# lab4.net
KiCad netlist of a schematic drawn in EAGLE
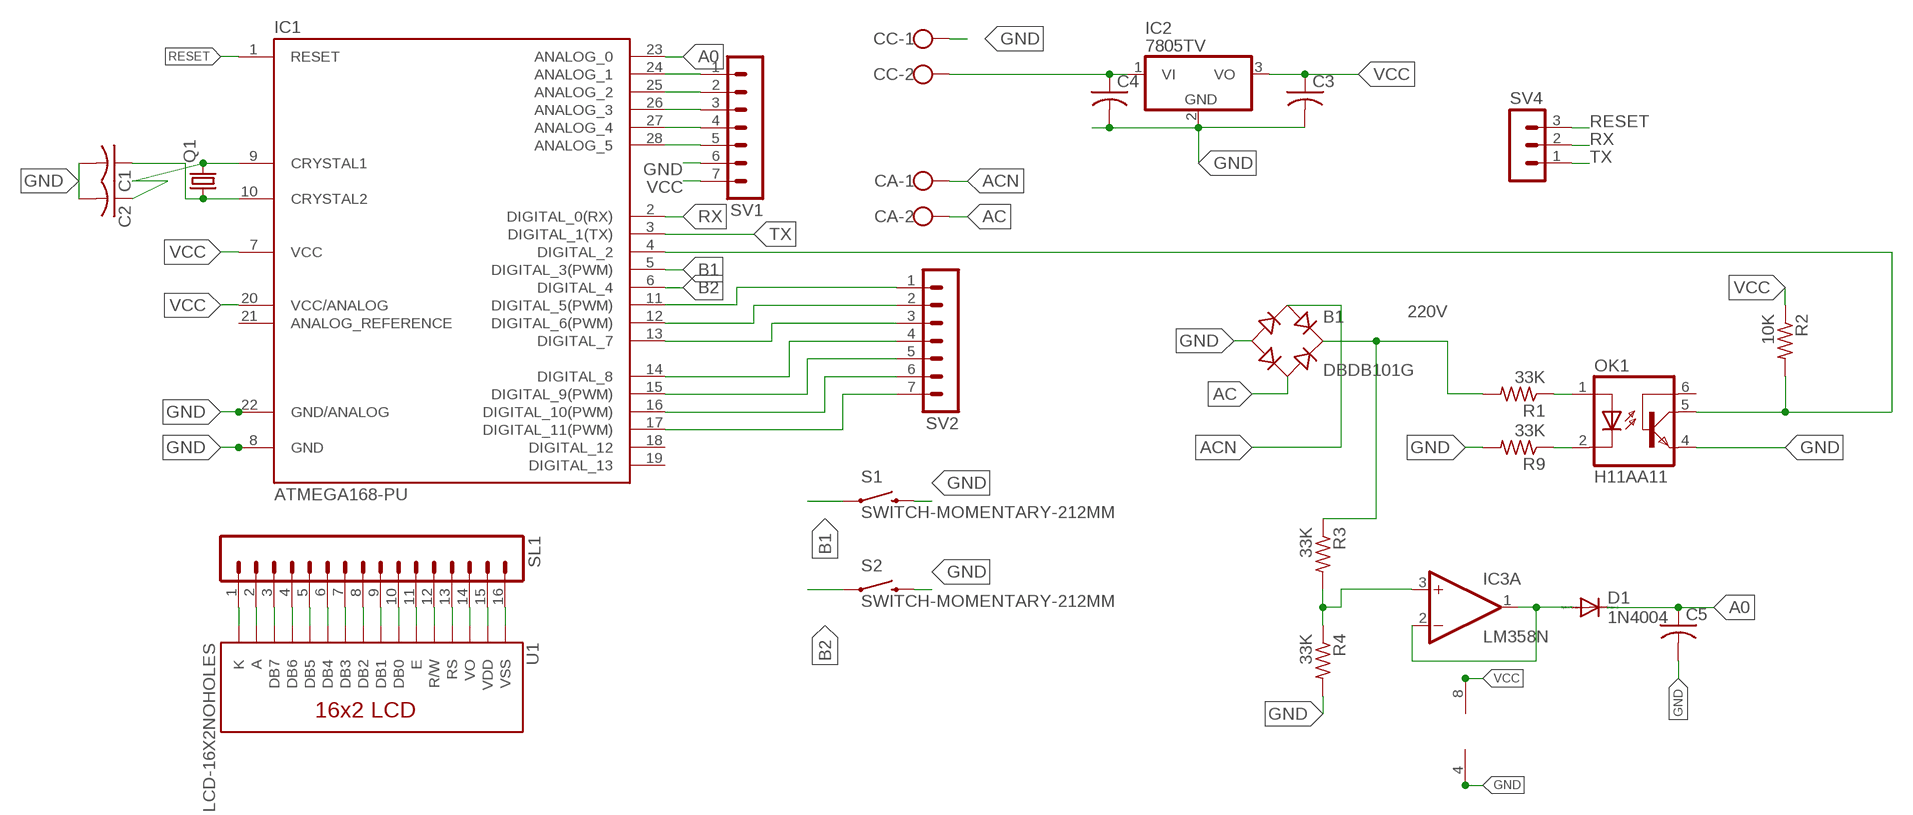
[diagram p0: schematic, sheet 1]

(export (version "E")
  (design (tool "Eeschema 10.0.6"))
  (components
    (comp (ref "B1")
      (value "DBDB101G")
      (footprint "eagle-import:DB")
      (libsource (lib "eagle-import") (part "DB?GDB101"))
    )
    (comp (ref "C1")
      (value "C-US025-025X050")
      (footprint "eagle-import:C025-025X050")
      (libsource (lib "eagle-import") (part "C-US025-025X050"))
    )
    (comp (ref "C2")
      (value "C-US025-025X050")
      (footprint "eagle-import:C025-025X050")
      (libsource (lib "eagle-import") (part "C-US025-025X050"))
    )
    (comp (ref "C3")
      (value "C-US075-032X103")
      (footprint "eagle-import:C075-032X103")
      (libsource (lib "eagle-import") (part "C-US075-032X103"))
    )
    (comp (ref "C4")
      (value "C-US050-025X075")
      (footprint "eagle-import:C050-025X075")
      (libsource (lib "eagle-import") (part "C-US050-025X075"))
    )
    (comp (ref "C5")
      (value "C-US050-075X075")
      (footprint "eagle-import:C050-075X075")
      (libsource (lib "eagle-import") (part "C-US050-075X075"))
    )
    (comp (ref "CA")
      (value "W237-102")
      (footprint "eagle-import:W237-102")
      (fields (field (name "MPN") "237-102"))
      (libsource (lib "eagle-import") (part "W237-102"))
    )
    (comp (ref "CC")
      (value "W237-102")
      (footprint "eagle-import:W237-102")
      (fields (field (name "MPN") "237-102"))
      (libsource (lib "eagle-import") (part "W237-102"))
    )
    (comp (ref "D1")
      (value "1N4004")
      (footprint "eagle-import:DO41-10")
      (libsource (lib "eagle-import") (part "1N4004"))
    )
    (comp (ref "IC1")
      (value "ATMEGA168-PU")
      (footprint "eagle-import:DIL28-3")
      (libsource (lib "eagle-import") (part "ATMEGA168-PU"))
    )
    (comp (ref "IC2")
      (value "7805TV")
      (footprint "eagle-import:TO220V")
      (libsource (lib "eagle-import") (part "78TV05"))
    )
    (comp (ref "IC3")
      (value "LM358N")
      (footprint "eagle-import:DIL08")
      (libsource (lib "eagle-import") (part "LM358N"))
    )
    (comp (ref "OK1")
      (value "H11AA11")
      (footprint "eagle-import:DIL06")
      (fields (field (name "MPN") "H11A1-M"))
      (libsource (lib "eagle-import") (part "H11AA11"))
    )
    (comp (ref "Q1")
      (value "CRYSTALHC18U-V")
      (footprint "eagle-import:HC18U-V")
      (libsource (lib "eagle-import") (part "CRYSTALHC18U-V"))
    )
    (comp (ref "R1")
      (value "33K")
      (footprint "eagle-import:0207_7")
      (libsource (lib "eagle-import") (part "R-US_0207/7"))
    )
    (comp (ref "R2")
      (value "10K")
      (footprint "eagle-import:0309_12")
      (libsource (lib "eagle-import") (part "R-US_0309/12"))
    )
    (comp (ref "R3")
      (value "33K")
      (footprint "eagle-import:0207_7")
      (libsource (lib "eagle-import") (part "R-US_0207/7"))
    )
    (comp (ref "R4")
      (value "33K")
      (footprint "eagle-import:0207_7")
      (libsource (lib "eagle-import") (part "R-US_0207/7"))
    )
    (comp (ref "R9")
      (value "33K")
      (footprint "eagle-import:0207_7")
      (libsource (lib "eagle-import") (part "R-US_0207/7"))
    )
    (comp (ref "S1")
      (value "SWITCH-MOMENTARY-212MM")
      (footprint "eagle-import:TACTILE-PTH-12MM")
      (libsource (lib "eagle-import") (part "SWITCH-MOMENTARY-212MM"))
    )
    (comp (ref "S2")
      (value "SWITCH-MOMENTARY-212MM")
      (footprint "eagle-import:TACTILE-PTH-12MM")
      (libsource (lib "eagle-import") (part "SWITCH-MOMENTARY-212MM"))
    )
    (comp (ref "SL1")
      (value "MA16")
      (footprint "eagle-import:16PA")
      (libsource (lib "eagle-import") (part "MA16"))
    )
    (comp (ref "SV1")
      (value "MA07-1")
      (footprint "eagle-import:MA07-1")
      (libsource (lib "eagle-import") (part "MA07-1"))
    )
    (comp (ref "SV2")
      (value "MA07-1")
      (footprint "eagle-import:MA07-1")
      (libsource (lib "eagle-import") (part "MA07-1"))
    )
    (comp (ref "SV4")
      (value "MA03-1")
      (footprint "eagle-import:MA03-1")
      (libsource (lib "eagle-import") (part "MA03-1"))
    )
    (comp (ref "U1")
      (value "LCD-16X2NOHOLES")
      (footprint "eagle-import:LCD-16X2_NOHOLES")
      (libsource (lib "eagle-import") (part "LCD-16X2NOHOLES"))
    )
  )
  (nets
    (net (code "1") (name "/220V") (class "Default")
      (node (ref "B1") (pin "+") (pinfunction "+_+") (pintype "passive"))
      (node (ref "R1") (pin "2") (pinfunction "2_2") (pintype "passive"))
      (node (ref "R3") (pin "1") (pinfunction "1_1") (pintype "passive"))
    )
    (net (code "2") (name "A0") (class "Default")
      (node (ref "C5") (pin "1") (pinfunction "1_1") (pintype "passive"))
      (node (ref "D1") (pin "C") (pinfunction "C_C") (pintype "passive"))
      (node (ref "IC1") (pin "23") (pinfunction "ANALOG_0_23") (pintype "bidirectional"))
    )
    (net (code "3") (name "AC") (class "Default")
      (node (ref "B1") (pin "AC2") (pinfunction "AC2_AC2") (pintype "passive"))
      (node (ref "CA") (pin "2") (pinfunction "KL_2") (pintype "passive"))
    )
    (net (code "4") (name "ACN") (class "Default")
      (node (ref "B1") (pin "AC1") (pinfunction "AC1_AC1") (pintype "passive"))
      (node (ref "CA") (pin "1") (pinfunction "KL_1") (pintype "passive"))
    )
    (net (code "5") (name "B1") (class "Default")
      (node (ref "IC1") (pin "5") (pinfunction "DIGITAL_3(PWM)_5") (pintype "bidirectional"))
      (node (ref "S1") (pin "1") (pinfunction "1_1") (pintype "passive"))
    )
    (net (code "6") (name "B2") (class "Default")
      (node (ref "IC1") (pin "6") (pinfunction "DIGITAL_4_6") (pintype "bidirectional"))
      (node (ref "S2") (pin "1") (pinfunction "1_1") (pintype "passive"))
    )
    (net (code "7") (name "GND") (class "Default")
      (node (ref "B1") (pin "-") (pinfunction "-_-") (pintype "passive"))
      (node (ref "C1") (pin "2") (pinfunction "2_2") (pintype "passive"))
      (node (ref "C2") (pin "2") (pinfunction "2_2") (pintype "passive"))
      (node (ref "C3") (pin "2") (pinfunction "2_2") (pintype "passive"))
      (node (ref "C4") (pin "2") (pinfunction "2_2") (pintype "passive"))
      (node (ref "C5") (pin "2") (pinfunction "2_2") (pintype "passive"))
      (node (ref "CC") (pin "1") (pinfunction "KL_1") (pintype "passive"))
      (node (ref "IC1") (pin "22") (pinfunction "GND/ANALOG_22") (pintype "power_in"))
      (node (ref "IC1") (pin "8") (pinfunction "GND_8") (pintype "power_in"))
      (node (ref "IC2") (pin "2") (pinfunction "GND_2") (pintype "passive"))
      (node (ref "IC3") (pin "4") (pinfunction "V-_4") (pintype "power_in"))
      (node (ref "OK1") (pin "4") (pinfunction "EMI_4") (pintype "passive"))
      (node (ref "R4") (pin "2") (pinfunction "2_2") (pintype "passive"))
      (node (ref "R9") (pin "2") (pinfunction "2_2") (pintype "passive"))
      (node (ref "S1") (pin "3") (pinfunction "2_3") (pintype "passive"))
      (node (ref "S2") (pin "3") (pinfunction "2_3") (pintype "passive"))
      (node (ref "SV1") (pin "6") (pinfunction "6_6") (pintype "passive"))
    )
    (net (code "8") (name "Net-(CCB-KL)") (class "Default")
      (node (ref "C4") (pin "1") (pinfunction "1_1") (pintype "passive"))
      (node (ref "CC") (pin "2") (pinfunction "KL_2") (pintype "passive"))
      (node (ref "IC2") (pin "1") (pinfunction "VI_1") (pintype "input"))
    )
    (net (code "9") (name "Net-(IC1-ANALOG_1)") (class "Default")
      (node (ref "IC1") (pin "24") (pinfunction "ANALOG_1_24") (pintype "bidirectional"))
      (node (ref "SV1") (pin "1") (pinfunction "1_1") (pintype "passive"))
    )
    (net (code "10") (name "Net-(IC1-ANALOG_2)") (class "Default")
      (node (ref "IC1") (pin "25") (pinfunction "ANALOG_2_25") (pintype "bidirectional"))
      (node (ref "SV1") (pin "2") (pinfunction "2_2") (pintype "passive"))
    )
    (net (code "11") (name "Net-(IC1-ANALOG_3)") (class "Default")
      (node (ref "IC1") (pin "26") (pinfunction "ANALOG_3_26") (pintype "bidirectional"))
      (node (ref "SV1") (pin "3") (pinfunction "3_3") (pintype "passive"))
    )
    (net (code "12") (name "Net-(IC1-ANALOG_4)") (class "Default")
      (node (ref "IC1") (pin "27") (pinfunction "ANALOG_4_27") (pintype "bidirectional"))
      (node (ref "SV1") (pin "4") (pinfunction "4_4") (pintype "passive"))
    )
    (net (code "13") (name "Net-(IC1-ANALOG_5)") (class "Default")
      (node (ref "IC1") (pin "28") (pinfunction "ANALOG_5_28") (pintype "bidirectional"))
      (node (ref "SV1") (pin "5") (pinfunction "5_5") (pintype "passive"))
    )
    (net (code "14") (name "Net-(IC1-CRYSTAL1)") (class "Default")
      (node (ref "C2") (pin "1") (pinfunction "1_1") (pintype "passive"))
      (node (ref "IC1") (pin "9") (pinfunction "CRYSTAL1_9") (pintype "bidirectional"))
      (node (ref "Q1") (pin "2") (pinfunction "2_2") (pintype "passive"))
    )
    (net (code "15") (name "Net-(IC1-CRYSTAL2)") (class "Default")
      (node (ref "C1") (pin "1") (pinfunction "1_1") (pintype "passive"))
      (node (ref "IC1") (pin "10") (pinfunction "CRYSTAL2_10") (pintype "bidirectional"))
      (node (ref "Q1") (pin "1") (pinfunction "1_1") (pintype "passive"))
    )
    (net (code "16") (name "Net-(IC1-DIGITAL_2)") (class "Default")
      (node (ref "IC1") (pin "4") (pinfunction "DIGITAL_2_4") (pintype "bidirectional"))
      (node (ref "OK1") (pin "5") (pinfunction "COL_5") (pintype "passive"))
      (node (ref "R2") (pin "2") (pinfunction "2_2") (pintype "passive"))
    )
    (net (code "17") (name "Net-(IC1-DIGITAL_5(PWM))") (class "Default")
      (node (ref "IC1") (pin "11") (pinfunction "DIGITAL_5(PWM)_11") (pintype "bidirectional"))
      (node (ref "SV2") (pin "1") (pinfunction "1_1") (pintype "passive"))
    )
    (net (code "18") (name "Net-(IC1-DIGITAL_6(PWM))") (class "Default")
      (node (ref "IC1") (pin "12") (pinfunction "DIGITAL_6(PWM)_12") (pintype "bidirectional"))
      (node (ref "SV2") (pin "2") (pinfunction "2_2") (pintype "passive"))
    )
    (net (code "19") (name "Net-(IC1-DIGITAL_7)") (class "Default")
      (node (ref "IC1") (pin "13") (pinfunction "DIGITAL_7_13") (pintype "bidirectional"))
      (node (ref "SV2") (pin "3") (pinfunction "3_3") (pintype "passive"))
    )
    (net (code "20") (name "Net-(IC1-DIGITAL_8)") (class "Default")
      (node (ref "IC1") (pin "14") (pinfunction "DIGITAL_8_14") (pintype "bidirectional"))
      (node (ref "SV2") (pin "4") (pinfunction "4_4") (pintype "passive"))
    )
    (net (code "21") (name "Net-(IC1-DIGITAL_9(PWM))") (class "Default")
      (node (ref "IC1") (pin "15") (pinfunction "DIGITAL_9(PWM)_15") (pintype "bidirectional"))
      (node (ref "SV2") (pin "5") (pinfunction "5_5") (pintype "passive"))
    )
    (net (code "22") (name "Net-(IC1-DIGITAL_10(PWM))") (class "Default")
      (node (ref "IC1") (pin "16") (pinfunction "DIGITAL_10(PWM)_16") (pintype "bidirectional"))
      (node (ref "SV2") (pin "6") (pinfunction "6_6") (pintype "passive"))
    )
    (net (code "23") (name "Net-(IC1-DIGITAL_11(PWM))") (class "Default")
      (node (ref "IC1") (pin "17") (pinfunction "DIGITAL_11(PWM)_17") (pintype "bidirectional"))
      (node (ref "SV2") (pin "7") (pinfunction "7_7") (pintype "passive"))
    )
    (net (code "24") (name "Net-(IC3A-+IN)") (class "Default")
      (node (ref "IC3") (pin "3") (pinfunction "+IN_3") (pintype "input"))
      (node (ref "R3") (pin "2") (pinfunction "2_2") (pintype "passive"))
      (node (ref "R4") (pin "1") (pinfunction "1_1") (pintype "passive"))
    )
    (net (code "25") (name "Net-(IC3A--IN)") (class "Default")
      (node (ref "D1") (pin "A") (pinfunction "A_A") (pintype "passive"))
      (node (ref "IC3") (pin "1") (pinfunction "OUT_1") (pintype "output"))
      (node (ref "IC3") (pin "2") (pinfunction "-IN_2") (pintype "input"))
    )
    (net (code "26") (name "Net-(OK1-A)") (class "Default")
      (node (ref "OK1") (pin "1") (pinfunction "A_1") (pintype "passive"))
      (node (ref "R1") (pin "1") (pinfunction "1_1") (pintype "passive"))
    )
    (net (code "27") (name "Net-(OK1-C)") (class "Default")
      (node (ref "OK1") (pin "2") (pinfunction "C_2") (pintype "passive"))
      (node (ref "R9") (pin "1") (pinfunction "1_1") (pintype "passive"))
    )
    (net (code "28") (name "Net-(U1-A)") (class "Default")
      (node (ref "SL1") (pin "2") (pinfunction "2_2") (pintype "passive"))
      (node (ref "U1") (pin "15") (pinfunction "A_15") (pintype "power_in"))
    )
    (net (code "29") (name "Net-(U1-DB0)") (class "Default")
      (node (ref "SL1") (pin "10") (pinfunction "10_10") (pintype "passive"))
      (node (ref "U1") (pin "7") (pinfunction "DB0_7") (pintype "bidirectional"))
    )
    (net (code "30") (name "Net-(U1-DB1)") (class "Default")
      (node (ref "SL1") (pin "9") (pinfunction "9_9") (pintype "passive"))
      (node (ref "U1") (pin "8") (pinfunction "DB1_8") (pintype "bidirectional"))
    )
    (net (code "31") (name "Net-(U1-DB2)") (class "Default")
      (node (ref "SL1") (pin "8") (pinfunction "8_8") (pintype "passive"))
      (node (ref "U1") (pin "9") (pinfunction "DB2_9") (pintype "bidirectional"))
    )
    (net (code "32") (name "Net-(U1-DB3)") (class "Default")
      (node (ref "SL1") (pin "7") (pinfunction "7_7") (pintype "passive"))
      (node (ref "U1") (pin "10") (pinfunction "DB3_10") (pintype "bidirectional"))
    )
    (net (code "33") (name "Net-(U1-DB4)") (class "Default")
      (node (ref "SL1") (pin "6") (pinfunction "6_6") (pintype "passive"))
      (node (ref "U1") (pin "11") (pinfunction "DB4_11") (pintype "bidirectional"))
    )
    (net (code "34") (name "Net-(U1-DB5)") (class "Default")
      (node (ref "SL1") (pin "5") (pinfunction "5_5") (pintype "passive"))
      (node (ref "U1") (pin "12") (pinfunction "DB5_12") (pintype "bidirectional"))
    )
    (net (code "35") (name "Net-(U1-DB6)") (class "Default")
      (node (ref "SL1") (pin "4") (pinfunction "4_4") (pintype "passive"))
      (node (ref "U1") (pin "13") (pinfunction "DB6_13") (pintype "bidirectional"))
    )
    (net (code "36") (name "Net-(U1-DB7)") (class "Default")
      (node (ref "SL1") (pin "3") (pinfunction "3_3") (pintype "passive"))
      (node (ref "U1") (pin "14") (pinfunction "DB7_14") (pintype "bidirectional"))
    )
    (net (code "37") (name "Net-(U1-E)") (class "Default")
      (node (ref "SL1") (pin "11") (pinfunction "11_11") (pintype "passive"))
      (node (ref "U1") (pin "6") (pinfunction "E_6") (pintype "input"))
    )
    (net (code "38") (name "Net-(U1-K)") (class "Default")
      (node (ref "SL1") (pin "1") (pinfunction "1_1") (pintype "passive"))
      (node (ref "U1") (pin "16") (pinfunction "K_16") (pintype "power_in"))
    )
    (net (code "39") (name "Net-(U1-RS)") (class "Default")
      (node (ref "SL1") (pin "13") (pinfunction "13_13") (pintype "passive"))
      (node (ref "U1") (pin "4") (pinfunction "RS_4") (pintype "input"))
    )
    (net (code "40") (name "Net-(U1-R{slash}W)") (class "Default")
      (node (ref "SL1") (pin "12") (pinfunction "12_12") (pintype "passive"))
      (node (ref "U1") (pin "5") (pinfunction "R/W_5") (pintype "input"))
    )
    (net (code "41") (name "Net-(U1-VDD)") (class "Default")
      (node (ref "SL1") (pin "15") (pinfunction "15_15") (pintype "passive"))
      (node (ref "U1") (pin "2") (pinfunction "VDD_2") (pintype "power_in"))
    )
    (net (code "42") (name "Net-(U1-VO)") (class "Default")
      (node (ref "SL1") (pin "14") (pinfunction "14_14") (pintype "passive"))
      (node (ref "U1") (pin "3") (pinfunction "VO_3") (pintype "bidirectional"))
    )
    (net (code "43") (name "Net-(U1-VSS)") (class "Default")
      (node (ref "SL1") (pin "16") (pinfunction "16_16") (pintype "passive"))
      (node (ref "U1") (pin "1") (pinfunction "VSS_1") (pintype "power_in"))
    )
    (net (code "44") (name "RESET") (class "Default")
      (node (ref "IC1") (pin "1") (pinfunction "RESET_1") (pintype "bidirectional"))
      (node (ref "SV4") (pin "3") (pinfunction "3_3") (pintype "passive"))
    )
    (net (code "45") (name "RX") (class "Default")
      (node (ref "IC1") (pin "2") (pinfunction "DIGITAL_0(RX)_2") (pintype "bidirectional"))
      (node (ref "SV4") (pin "2") (pinfunction "2_2") (pintype "passive"))
    )
    (net (code "46") (name "TX") (class "Default")
      (node (ref "IC1") (pin "3") (pinfunction "DIGITAL_1(TX)_3") (pintype "bidirectional"))
      (node (ref "SV4") (pin "1") (pinfunction "1_1") (pintype "passive"))
    )
    (net (code "47") (name "VCC") (class "Default")
      (node (ref "C3") (pin "1") (pinfunction "1_1") (pintype "passive"))
      (node (ref "IC1") (pin "20") (pinfunction "VCC/ANALOG_20") (pintype "passive"))
      (node (ref "IC1") (pin "7") (pinfunction "VCC_7") (pintype "power_in"))
      (node (ref "IC2") (pin "3") (pinfunction "VO_3") (pintype "passive"))
      (node (ref "IC3") (pin "8") (pinfunction "V+_8") (pintype "power_in"))
      (node (ref "R2") (pin "1") (pinfunction "1_1") (pintype "passive"))
      (node (ref "SV1") (pin "7") (pinfunction "7_7") (pintype "passive"))
    )
    (net (code "48") (name "unconnected-(IC1-ANALOG_REFERENCE-Pad21)") (class "Default")
      (node (ref "IC1") (pin "21") (pinfunction "ANALOG_REFERENCE_21") (pintype "passive"))
    )
    (net (code "49") (name "unconnected-(IC1-DIGITAL_12-Pad18)") (class "Default")
      (node (ref "IC1") (pin "18") (pinfunction "DIGITAL_12_18") (pintype "bidirectional"))
    )
    (net (code "50") (name "unconnected-(IC1-DIGITAL_13-Pad19)") (class "Default")
      (node (ref "IC1") (pin "19") (pinfunction "DIGITAL_13_19") (pintype "bidirectional"))
    )
    (net (code "51") (name "unconnected-(OK1-BAS-Pad6)") (class "Default")
      (node (ref "OK1") (pin "6") (pinfunction "BAS_6") (pintype "passive"))
    )
  )
)
